# Power_Supply.net
KiCad netlist of a schematic drawn in Altium Designer
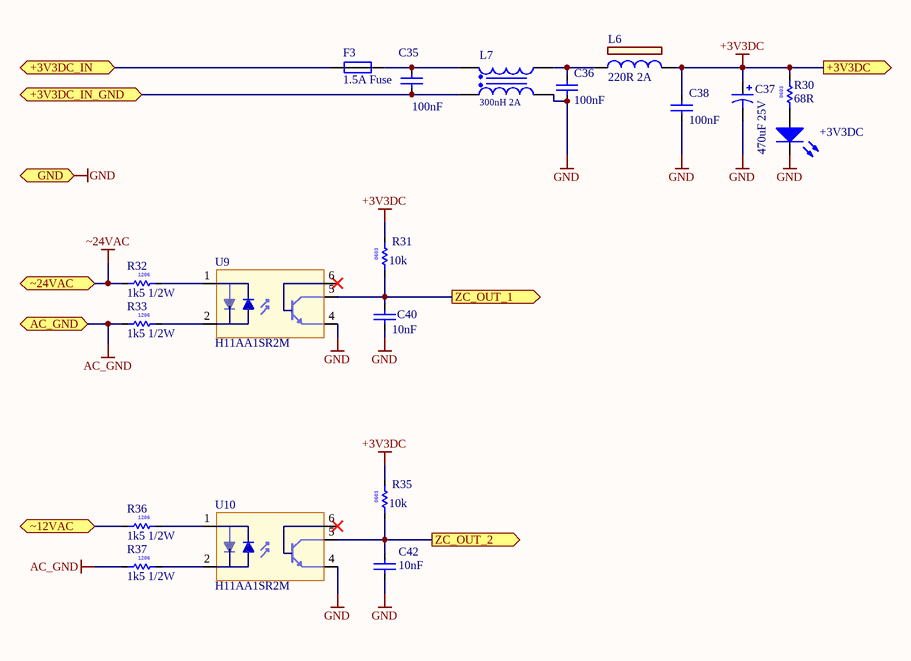
[diagram p0: Power_Supply.SchDoc]

(export (version "E")
  (design (tool "Eeschema 10.0.6"))
  (components
    (comp (ref "+3V3DC")
      (value "Green LED")
      (footprint "LED_GRN")
      (description "KPT-2012SGC -  LED, Low Power, Green, SMD, 2mm x 1.25mm, 20 mA, 2.2 V, 568 nm")
      (libsource (lib "AV_Lib_200418") (part "KPT-2012SGC"))
    )
    (comp (ref "C35") (value "100nF") (footprint "CAPC1608N") (libsource (lib "DB") (part "C_SM")))
    (comp (ref "C36") (value "100nF") (footprint "CAPC1608N") (libsource (lib "DB") (part "C_SM")))
    (comp (ref "C37")
      (value "470uF 25V")
      (footprint "10X10.5")
      (libsource (lib "AV_Lib_200418") (part "470uF 25V"))
    )
    (comp (ref "C38") (value "100nF") (footprint "CAPC1608N") (libsource (lib "DB") (part "C_SM")))
    (comp (ref "C40") (value "10nF") (footprint "CAPC1608N") (libsource (lib "DB") (part "C_SM")))
    (comp (ref "C42") (value "10nF") (footprint "CAPC1608N") (libsource (lib "DB") (part "C_SM")))
    (comp (ref "F3")
      (value "1.5A Fuse")
      (footprint "1206F")
      (description "MCCFB1206TFF/1.5 -  Fuse, Surface Mount, 1.5 A, 32 V, Fast Acting, 1206")
      (libsource (lib "AV_Lib_200418") (part "1.5A Fuse"))
    )
    (comp (ref "L6")
      (value "220R 2A")
      (footprint "LL0805\\2P")
      (description "BLM21PG221SN1D -  Ferrite Bead, 0805 [2012 Metric], 220 ohm, 2 A, BLM21P Series, 0.045 ohm, ± 25%")
      (libsource (lib "DB") (part "L_core"))
    )
    (comp (ref "L7")
      (value "300nH 2A")
      (footprint "1812_CM_WE")
      (description "744235900 -  Filter, Line, Common Mode, 300 nH, WE-CNSW Series, 90 ohm, 2 A, 4.5mm x 3.2mm x 2.8mm")
      (libsource (lib "AV_Lib_200418") (part "300 nH"))
    )
    (comp (ref "R30") (value "68R") (footprint "RESC1608N") (libsource (lib "DB") (part "R0603")))
    (comp (ref "R31") (value "10k") (footprint "RESC1608N") (libsource (lib "DB") (part "R0603")))
    (comp (ref "R32") (value "1k5 1/2W") (footprint "RESC3216N") (libsource (lib "DB") (part "R1206")))
    (comp (ref "R33") (value "1k5 1/2W") (footprint "RESC3216N") (libsource (lib "DB") (part "R1206")))
    (comp (ref "R35") (value "10k") (footprint "RESC1608N") (libsource (lib "DB") (part "R0603")))
    (comp (ref "R36") (value "1k5 1/2W") (footprint "RESC3216N") (libsource (lib "DB") (part "R1206")))
    (comp (ref "R37") (value "1k5 1/2W") (footprint "RESC3216N") (libsource (lib "DB") (part "R1206")))
    (comp (ref "U9")
      (value "H11AA1SR2M")
      (footprint "SMDIP-6")
      (libsource (lib "AV_Lib_200418") (part "H11AA1SR2M"))
    )
    (comp (ref "U10")
      (value "H11AA1SR2M")
      (footprint "SMDIP-6")
      (libsource (lib "AV_Lib_200418") (part "H11AA1SR2M"))
    )
  )
  (nets
    (net (code "1") (name "+3V3DC") (class "Default")
      (node (ref "C37") (pin "1") (pinfunction "1_1") (pintype "passive"))
      (node (ref "C38") (pin "2") (pinfunction "2_2") (pintype "passive"))
      (node (ref "L6") (pin "2") (pinfunction "2_2") (pintype "passive"))
      (node (ref "R30") (pin "2") (pinfunction "2_2") (pintype "passive"))
      (node (ref "R31") (pin "2") (pinfunction "2_2") (pintype "passive"))
      (node (ref "R35") (pin "2") (pinfunction "2_2") (pintype "passive"))
    )
    (net (code "2") (name "/+3V3DC_IN") (class "Default")
      (node (ref "F3") (pin "1") (pinfunction "1_1") (pintype "passive"))
    )
    (net (code "3") (name "/+3V3DC_IN_GND") (class "Default")
      (node (ref "C35") (pin "1") (pinfunction "1_1") (pintype "passive"))
      (node (ref "L7") (pin "1") (pinfunction "1_1") (pintype "passive"))
    )
    (net (code "4") (name "/ZC_OUT_1") (class "Default")
      (node (ref "C40") (pin "1") (pinfunction "1_1") (pintype "passive"))
      (node (ref "R31") (pin "1") (pinfunction "1_1") (pintype "passive"))
      (node (ref "U9") (pin "5") (pinfunction "C_5") (pintype "passive"))
    )
    (net (code "5") (name "/ZC_OUT_2") (class "Default")
      (node (ref "C42") (pin "1") (pinfunction "1_1") (pintype "passive"))
      (node (ref "R35") (pin "1") (pinfunction "1_1") (pintype "passive"))
      (node (ref "U10") (pin "5") (pinfunction "C_5") (pintype "passive"))
    )
    (net (code "6") (name "/~12VAC") (class "Default")
      (node (ref "R36") (pin "1") (pinfunction "1_1") (pintype "passive"))
    )
    (net (code "7") (name "AC_GND") (class "Default")
      (node (ref "R33") (pin "1") (pinfunction "1_1") (pintype "passive"))
      (node (ref "R37") (pin "1") (pinfunction "1_1") (pintype "passive"))
    )
    (net (code "8") (name "GND") (class "Default")
      (node (ref "+3V3DC") (pin "2") (pinfunction "K_2") (pintype "passive"))
      (node (ref "C36") (pin "1") (pinfunction "1_1") (pintype "passive"))
      (node (ref "C37") (pin "2") (pinfunction "2_2") (pintype "passive"))
      (node (ref "C38") (pin "1") (pinfunction "1_1") (pintype "passive"))
      (node (ref "C40") (pin "2") (pinfunction "2_2") (pintype "passive"))
      (node (ref "C42") (pin "2") (pinfunction "2_2") (pintype "passive"))
      (node (ref "L7") (pin "2") (pinfunction "2_2") (pintype "passive"))
      (node (ref "U10") (pin "4") (pinfunction "E_4") (pintype "passive"))
      (node (ref "U9") (pin "4") (pinfunction "E_4") (pintype "passive"))
    )
    (net (code "9") (name "Net-(+3V3DC-A)") (class "Default")
      (node (ref "+3V3DC") (pin "1") (pinfunction "A_1") (pintype "passive"))
      (node (ref "R30") (pin "1") (pinfunction "1_1") (pintype "passive"))
    )
    (net (code "10") (name "Net-(C35-Pad2)") (class "Default")
      (node (ref "C35") (pin "2") (pinfunction "2_2") (pintype "passive"))
      (node (ref "F3") (pin "2") (pinfunction "2_2") (pintype "passive"))
      (node (ref "L7") (pin "4") (pinfunction "4_4") (pintype "passive"))
    )
    (net (code "11") (name "Net-(C36-Pad2)") (class "Default")
      (node (ref "C36") (pin "2") (pinfunction "2_2") (pintype "passive"))
      (node (ref "L6") (pin "1") (pinfunction "1_1") (pintype "passive"))
      (node (ref "L7") (pin "3") (pinfunction "3_3") (pintype "passive"))
    )
    (net (code "12") (name "Net-(U9-A)") (class "Default")
      (node (ref "R32") (pin "2") (pinfunction "2_2") (pintype "passive"))
      (node (ref "U9") (pin "1") (pinfunction "A_1") (pintype "passive"))
    )
    (net (code "13") (name "Net-(U9-K)") (class "Default")
      (node (ref "R33") (pin "2") (pinfunction "2_2") (pintype "passive"))
      (node (ref "U9") (pin "2") (pinfunction "K_2") (pintype "passive"))
    )
    (net (code "14") (name "Net-(U10-A)") (class "Default")
      (node (ref "R36") (pin "2") (pinfunction "2_2") (pintype "passive"))
      (node (ref "U10") (pin "1") (pinfunction "A_1") (pintype "passive"))
    )
    (net (code "15") (name "Net-(U10-K)") (class "Default")
      (node (ref "R37") (pin "2") (pinfunction "2_2") (pintype "passive"))
      (node (ref "U10") (pin "2") (pinfunction "K_2") (pintype "passive"))
    )
    (net (code "16") (name "unconnected-(U9-B-Pad6)") (class "Default")
      (node (ref "U9") (pin "6") (pinfunction "B_6") (pintype "passive+no_connect"))
    )
    (net (code "17") (name "unconnected-(U10-B-Pad6)") (class "Default")
      (node (ref "U10") (pin "6") (pinfunction "B_6") (pintype "passive+no_connect"))
    )
    (net (code "18") (name "~24VAC") (class "Default")
      (node (ref "R32") (pin "1") (pinfunction "1_1") (pintype "passive"))
    )
  )
)
